# SparkFun_RFM97CW_Breakout.net
KiCad netlist of a schematic drawn in EAGLE
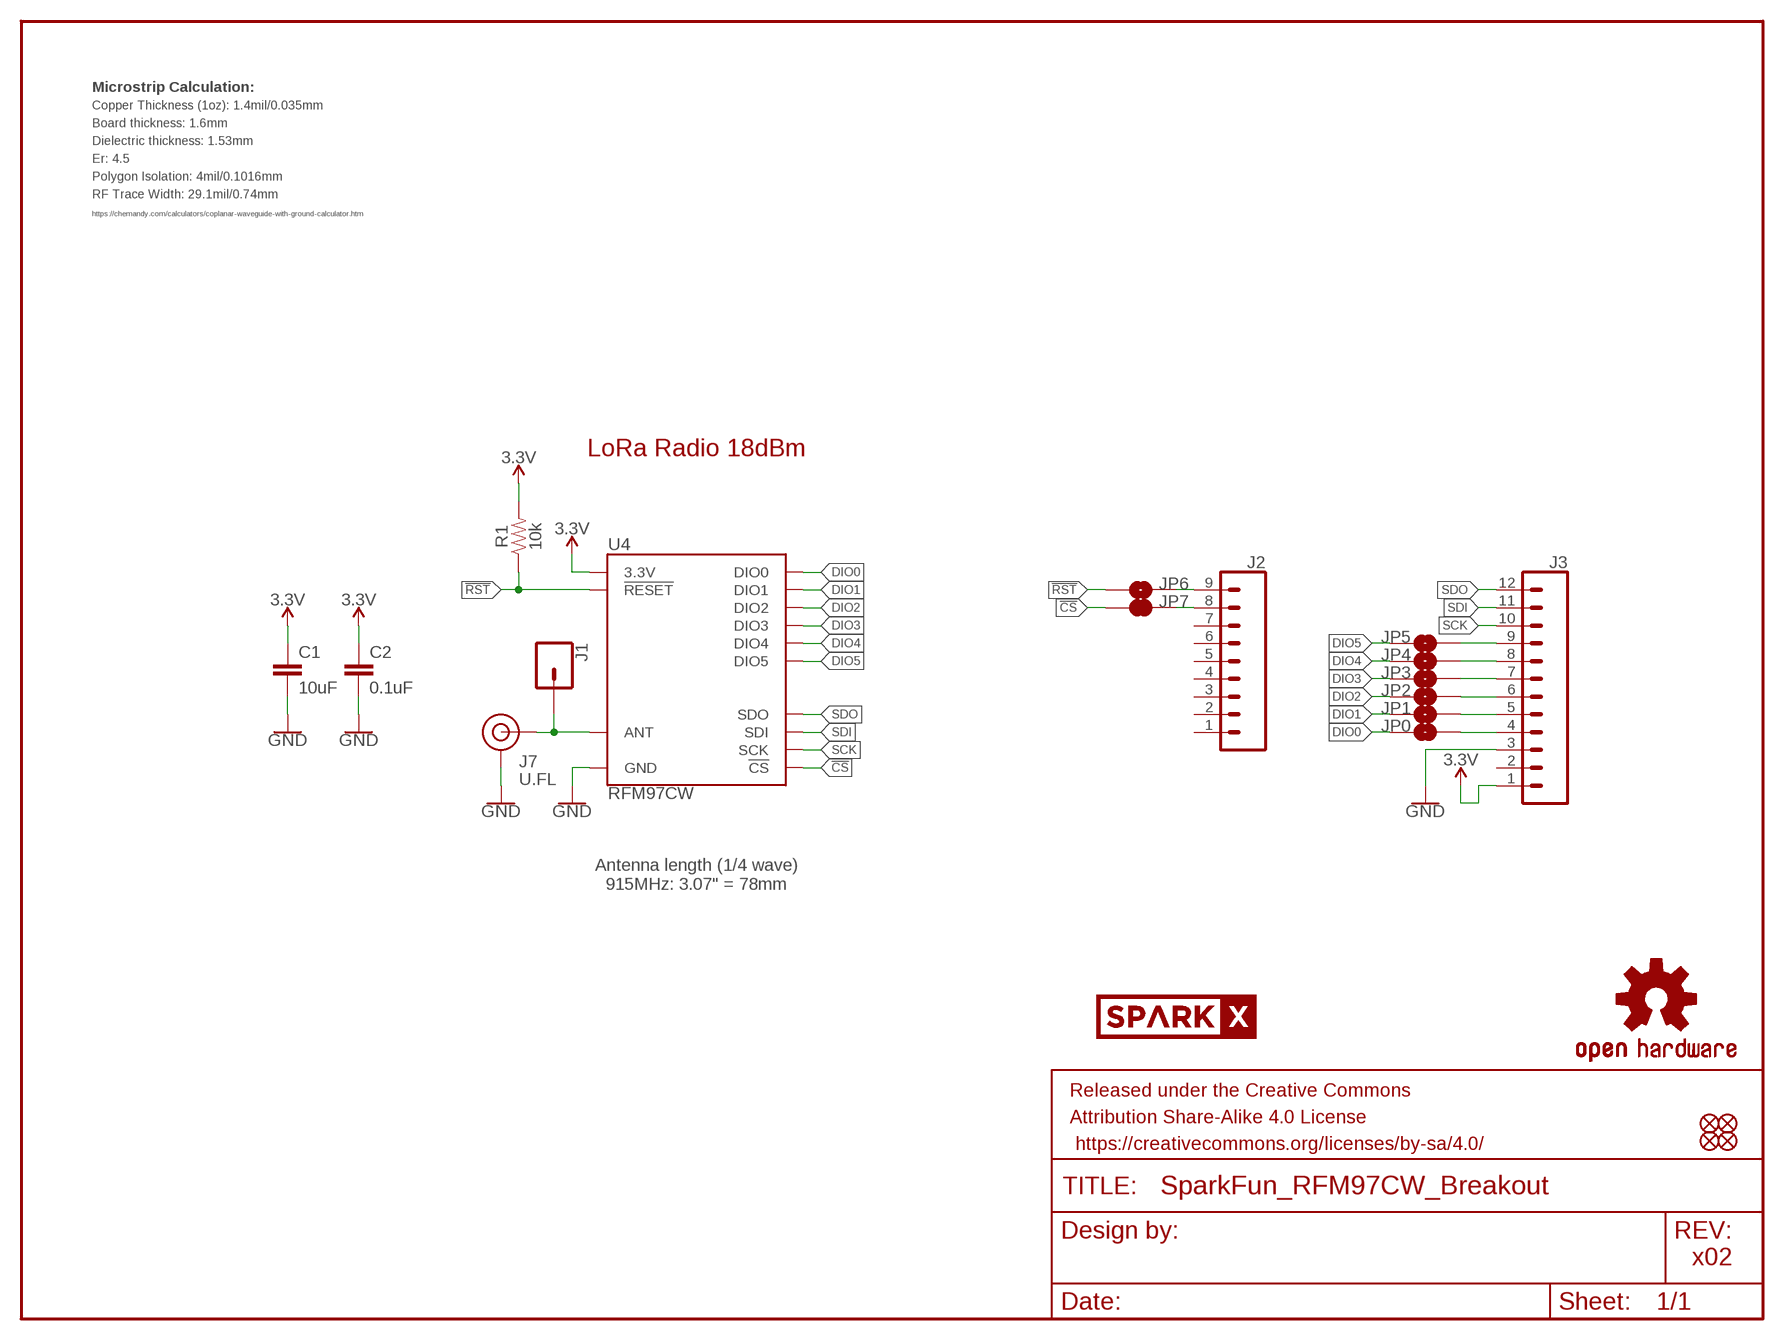
[diagram p0: schematic, sheet 1]

(export (version "E")
  (design (tool "Eeschema 10.0.6"))
  (components
    (comp (ref "C1")
      (value "10uF")
      (footprint "eagle-import:0603")
      (libsource (lib "eagle-import") (part "10UF-0603-6.3V-20%"))
    )
    (comp (ref "C2")
      (value "0.1uF")
      (footprint "eagle-import:0603")
      (libsource (lib "eagle-import") (part "0.1UF-0603-25V-(+80/-20%)"))
    )
    (comp (ref "FID1")
      (value "FIDUCIAL1X2")
      (footprint "eagle-import:FIDUCIAL-1X2")
      (libsource (lib "eagle-import") (part "FIDUCIAL1X2"))
    )
    (comp (ref "FID2")
      (value "FIDUCIAL1X2")
      (footprint "eagle-import:FIDUCIAL-1X2")
      (libsource (lib "eagle-import") (part "FIDUCIAL1X2"))
    )
    (comp (ref "FID3")
      (value "FIDUCIAL1X2")
      (footprint "eagle-import:FIDUCIAL-1X2")
      (libsource (lib "eagle-import") (part "FIDUCIAL1X2"))
    )
    (comp (ref "FID4")
      (value "FIDUCIAL1X2")
      (footprint "eagle-import:FIDUCIAL-1X2")
      (libsource (lib "eagle-import") (part "FIDUCIAL1X2"))
    )
    (comp (ref "FRAME1")
      (value "FRAME-LETTER")
      (footprint "eagle-import:CREATIVE_COMMONS")
      (libsource (lib "eagle-import") (part "FRAME-LETTER"))
    )
    (comp (ref "J1")
      (value "CONN_01PTH_NO_SILK_YES_STOP")
      (footprint "eagle-import:1X01_NO_SILK")
      (libsource (lib "eagle-import") (part "CONN_01PTH_NO_SILK_YES_STOP"))
    )
    (comp (ref "J2")
      (value "CONN_09NO_SILK")
      (footprint "eagle-import:1X09_NO_SILK")
      (libsource (lib "eagle-import") (part "CONN_09NO_SILK"))
    )
    (comp (ref "J3")
      (value "CONN_12NO_SILK")
      (footprint "eagle-import:1X12_NO_SILK")
      (libsource (lib "eagle-import") (part "CONN_12NO_SILK"))
    )
    (comp (ref "J7")
      (value "U.FL")
      (footprint "eagle-import:U.FL")
      (libsource (lib "eagle-import") (part "U.FL2PIN"))
    )
    (comp (ref "JP0")
      (value "JUMPER-SMT_2_NO_NO-SILK")
      (footprint "eagle-import:SMT-JUMPER_2_NO_NO-SILK")
      (libsource (lib "eagle-import") (part "JUMPER-SMT_2_NO_NO-SILK"))
    )
    (comp (ref "JP1")
      (value "JUMPER-SMT_2_NO_NO-SILK")
      (footprint "eagle-import:SMT-JUMPER_2_NO_NO-SILK")
      (libsource (lib "eagle-import") (part "JUMPER-SMT_2_NO_NO-SILK"))
    )
    (comp (ref "JP2")
      (value "JUMPER-SMT_2_NO_NO-SILK")
      (footprint "eagle-import:SMT-JUMPER_2_NO_NO-SILK")
      (libsource (lib "eagle-import") (part "JUMPER-SMT_2_NO_NO-SILK"))
    )
    (comp (ref "JP3")
      (value "JUMPER-SMT_2_NO_NO-SILK")
      (footprint "eagle-import:SMT-JUMPER_2_NO_NO-SILK")
      (libsource (lib "eagle-import") (part "JUMPER-SMT_2_NO_NO-SILK"))
    )
    (comp (ref "JP4")
      (value "JUMPER-SMT_2_NO_NO-SILK")
      (footprint "eagle-import:SMT-JUMPER_2_NO_NO-SILK")
      (libsource (lib "eagle-import") (part "JUMPER-SMT_2_NO_NO-SILK"))
    )
    (comp (ref "JP5")
      (value "JUMPER-SMT_2_NO_NO-SILK")
      (footprint "eagle-import:SMT-JUMPER_2_NO_NO-SILK")
      (libsource (lib "eagle-import") (part "JUMPER-SMT_2_NO_NO-SILK"))
    )
    (comp (ref "JP6")
      (value "JUMPER-SMT_2_NO_NO-SILK")
      (footprint "eagle-import:SMT-JUMPER_2_NO_NO-SILK")
      (libsource (lib "eagle-import") (part "JUMPER-SMT_2_NO_NO-SILK"))
    )
    (comp (ref "JP7")
      (value "JUMPER-SMT_2_NC_TRACE_NO-SILK")
      (footprint "eagle-import:SMT-JUMPER_2_NC_TRACE_NO-SILK")
      (libsource (lib "eagle-import") (part "JUMPER-SMT_2_NC_TRACE_NO-SILK"))
    )
    (comp (ref "LOGO2")
      (value "OSHW-LOGOS")
      (footprint "eagle-import:OSHW-LOGO-S")
      (libsource (lib "eagle-import") (part "OSHW-LOGOS"))
    )
    (comp (ref "R1")
      (value "10k")
      (footprint "eagle-import:0603")
      (libsource (lib "eagle-import") (part "10KOHM-0603-1/10W-1%"))
    )
    (comp (ref "U$22")
      (value "SPARKX-LOGO5")
      (footprint "eagle-import:SPARKX-LARGE")
      (libsource (lib "eagle-import") (part "SPARKX-LOGO5"))
    )
    (comp (ref "U4")
      (value "RFM97CW")
      (footprint "eagle-import:RFM97")
      (libsource (lib "eagle-import") (part "RFM9XRFM97"))
    )
  )
  (nets
    (net (code "1") (name "/~{CS}") (class "Default")
      (node (ref "JP7") (pin "1") (pinfunction "1_1") (pintype "passive"))
      (node (ref "U4") (pin "!CS!") (pinfunction "~{CS}_!CS!") (pintype "bidirectional"))
    )
    (net (code "2") (name "/~{RST}") (class "Default")
      (node (ref "JP6") (pin "1") (pinfunction "1_1") (pintype "passive"))
      (node (ref "R1") (pin "1") (pinfunction "1_1") (pintype "passive"))
      (node (ref "U4") (pin "!RST") (pinfunction "~{RESET}_!RST") (pintype "bidirectional"))
    )
    (net (code "3") (name "3.3V") (class "Default")
      (node (ref "C1") (pin "1") (pinfunction "1_1") (pintype "passive"))
      (node (ref "C2") (pin "1") (pinfunction "1_1") (pintype "passive"))
      (node (ref "J3") (pin "1") (pinfunction "1_1") (pintype "passive"))
      (node (ref "R1") (pin "2") (pinfunction "2_2") (pintype "passive"))
      (node (ref "U4") (pin "3V3") (pinfunction "3.3V_3V3") (pintype "bidirectional"))
    )
    (net (code "4") (name "DIO0") (class "Default")
      (node (ref "JP0") (pin "1") (pinfunction "1_1") (pintype "passive"))
      (node (ref "U4") (pin "DIO0") (pinfunction "DIO0_DIO0") (pintype "bidirectional"))
    )
    (net (code "5") (name "DIO1") (class "Default")
      (node (ref "JP1") (pin "1") (pinfunction "1_1") (pintype "passive"))
      (node (ref "U4") (pin "DIO1") (pinfunction "DIO1_DIO1") (pintype "bidirectional"))
    )
    (net (code "6") (name "DIO2") (class "Default")
      (node (ref "JP2") (pin "1") (pinfunction "1_1") (pintype "passive"))
      (node (ref "U4") (pin "DIO2") (pinfunction "DIO2_DIO2") (pintype "bidirectional"))
    )
    (net (code "7") (name "DIO3") (class "Default")
      (node (ref "JP3") (pin "1") (pinfunction "1_1") (pintype "passive"))
      (node (ref "U4") (pin "DIO3") (pinfunction "DIO3_DIO3") (pintype "bidirectional"))
    )
    (net (code "8") (name "DIO4") (class "Default")
      (node (ref "JP4") (pin "1") (pinfunction "1_1") (pintype "passive"))
      (node (ref "U4") (pin "DIO4") (pinfunction "DIO4_DIO4") (pintype "bidirectional"))
    )
    (net (code "9") (name "DIO5") (class "Default")
      (node (ref "JP5") (pin "1") (pinfunction "1_1") (pintype "passive"))
      (node (ref "U4") (pin "DIO5") (pinfunction "DIO5_DIO5") (pintype "bidirectional"))
    )
    (net (code "10") (name "GND") (class "Default")
      (node (ref "C1") (pin "2") (pinfunction "2_2") (pintype "passive"))
      (node (ref "C2") (pin "2") (pinfunction "2_2") (pintype "passive"))
      (node (ref "J3") (pin "3") (pinfunction "3_3") (pintype "passive"))
      (node (ref "J7") (pin "1") (pinfunction "GND_1") (pintype "bidirectional"))
      (node (ref "J7") (pin "2") (pinfunction "GND_2") (pintype "bidirectional"))
      (node (ref "U4") (pin "GND") (pinfunction "GND_GND") (pintype "bidirectional"))
      (node (ref "U4") (pin "GND@1") (pinfunction "GND_GND@1") (pintype "bidirectional"))
      (node (ref "U4") (pin "GND@2") (pinfunction "GND_GND@2") (pintype "bidirectional"))
    )
    (net (code "11") (name "Net-(J2-Pad8)") (class "Default")
      (node (ref "J2") (pin "8") (pinfunction "8_8") (pintype "passive"))
      (node (ref "JP7") (pin "2") (pinfunction "2_2") (pintype "passive"))
    )
    (net (code "12") (name "Net-(J2-Pad9)") (class "Default")
      (node (ref "J2") (pin "9") (pinfunction "9_9") (pintype "passive"))
      (node (ref "JP6") (pin "2") (pinfunction "2_2") (pintype "passive"))
    )
    (net (code "13") (name "Net-(J3-Pad4)") (class "Default")
      (node (ref "J3") (pin "4") (pinfunction "4_4") (pintype "passive"))
      (node (ref "JP0") (pin "2") (pinfunction "2_2") (pintype "passive"))
    )
    (net (code "14") (name "Net-(J3-Pad5)") (class "Default")
      (node (ref "J3") (pin "5") (pinfunction "5_5") (pintype "passive"))
      (node (ref "JP1") (pin "2") (pinfunction "2_2") (pintype "passive"))
    )
    (net (code "15") (name "Net-(J3-Pad6)") (class "Default")
      (node (ref "J3") (pin "6") (pinfunction "6_6") (pintype "passive"))
      (node (ref "JP2") (pin "2") (pinfunction "2_2") (pintype "passive"))
    )
    (net (code "16") (name "Net-(J3-Pad7)") (class "Default")
      (node (ref "J3") (pin "7") (pinfunction "7_7") (pintype "passive"))
      (node (ref "JP3") (pin "2") (pinfunction "2_2") (pintype "passive"))
    )
    (net (code "17") (name "Net-(J3-Pad8)") (class "Default")
      (node (ref "J3") (pin "8") (pinfunction "8_8") (pintype "passive"))
      (node (ref "JP4") (pin "2") (pinfunction "2_2") (pintype "passive"))
    )
    (net (code "18") (name "Net-(J3-Pad9)") (class "Default")
      (node (ref "J3") (pin "9") (pinfunction "9_9") (pintype "passive"))
      (node (ref "JP5") (pin "2") (pinfunction "2_2") (pintype "passive"))
    )
    (net (code "19") (name "Net-(J7-SIGNAL)") (class "Default")
      (node (ref "J1") (pin "1") (pinfunction "1_1") (pintype "passive"))
      (node (ref "J7") (pin "FEED") (pinfunction "SIGNAL_FEED") (pintype "bidirectional"))
      (node (ref "U4") (pin "ANT") (pinfunction "ANT_ANT") (pintype "bidirectional"))
    )
    (net (code "20") (name "SCK") (class "Default")
      (node (ref "J3") (pin "10") (pinfunction "10_10") (pintype "passive"))
      (node (ref "U4") (pin "SCK") (pinfunction "SCK_SCK") (pintype "bidirectional"))
    )
    (net (code "21") (name "SDI") (class "Default")
      (node (ref "J3") (pin "11") (pinfunction "11_11") (pintype "passive"))
      (node (ref "U4") (pin "SDI") (pinfunction "SDI_SDI") (pintype "bidirectional"))
    )
    (net (code "22") (name "SDO") (class "Default")
      (node (ref "J3") (pin "12") (pinfunction "12_12") (pintype "passive"))
      (node (ref "U4") (pin "SDO") (pinfunction "SDO_SDO") (pintype "bidirectional"))
    )
    (net (code "23") (name "unconnected-(J2-Pad1)") (class "Default")
      (node (ref "J2") (pin "1") (pinfunction "1_1") (pintype "passive"))
    )
    (net (code "24") (name "unconnected-(J2-Pad2)") (class "Default")
      (node (ref "J2") (pin "2") (pinfunction "2_2") (pintype "passive"))
    )
    (net (code "25") (name "unconnected-(J2-Pad3)") (class "Default")
      (node (ref "J2") (pin "3") (pinfunction "3_3") (pintype "passive"))
    )
    (net (code "26") (name "unconnected-(J2-Pad4)") (class "Default")
      (node (ref "J2") (pin "4") (pinfunction "4_4") (pintype "passive"))
    )
    (net (code "27") (name "unconnected-(J2-Pad5)") (class "Default")
      (node (ref "J2") (pin "5") (pinfunction "5_5") (pintype "passive"))
    )
    (net (code "28") (name "unconnected-(J2-Pad6)") (class "Default")
      (node (ref "J2") (pin "6") (pinfunction "6_6") (pintype "passive"))
    )
    (net (code "29") (name "unconnected-(J2-Pad7)") (class "Default")
      (node (ref "J2") (pin "7") (pinfunction "7_7") (pintype "passive"))
    )
    (net (code "30") (name "unconnected-(J3-Pad2)") (class "Default")
      (node (ref "J3") (pin "2") (pinfunction "2_2") (pintype "passive"))
    )
  )
)
